# 6_I2C_Sensors.net
KiCad netlist of a schematic drawn in Altium Designer
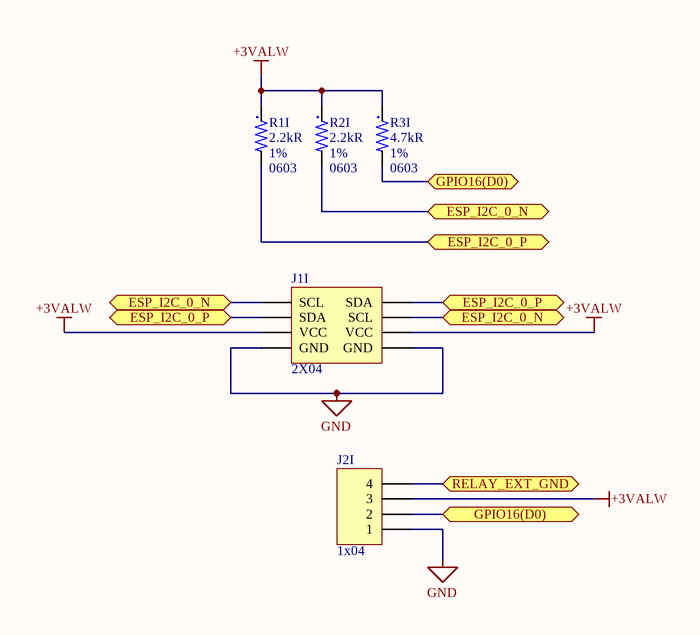
[diagram p0: 6_I2C_Sensors.SchDoc]

(export (version "E")
  (design (tool "Eeschema 10.0.6"))
  (components
    (comp (ref "J1I")
      (value "2X04")
      (footprint "PinHeader_2x04_P2.54mm_Vertical")
      (libsource (lib "Lib_Connector_PinHeader_2.54mm") (part "I2C_2X04_P2.54mm"))
    )
    (comp (ref "J2I")
      (value "1x04")
      (footprint "PinHeader_1x04_P2.54mm_Vertical")
      (libsource (lib "Lib_Connector_PinHeader_2.54mm") (part "PinHeader 1x04"))
    )
    (comp (ref "R1I")
      (value "2.2kR")
      (footprint "R0603-MFG")
      (description "SMD Chip Resistor, 2.2 kOhm, ± 1%, 100 mW, 0603 [1608 Metric], Thick Film, General Purpose")
      (fields
        (field (name "MANUFACTURER") "Yageo")
        (field (name "MANUFACTURER PART NUMBER") "RC0603FR-072K2L")
        (field (name "TOLERANCE") "1%")
        (field (name "CASE/PACKAGE") "0603")
      )
      (libsource (lib "Lib_Register_0603") (part "2.2K"))
    )
    (comp (ref "R2I")
      (value "2.2kR")
      (footprint "R0603-MFG")
      (description "SMD Chip Resistor, 2.2 kOhm, ± 1%, 100 mW, 0603 [1608 Metric], Thick Film, General Purpose")
      (fields
        (field (name "MANUFACTURER") "Yageo")
        (field (name "MANUFACTURER PART NUMBER") "RC0603FR-072K2L")
        (field (name "TOLERANCE") "1%")
        (field (name "CASE/PACKAGE") "0603")
      )
      (libsource (lib "Lib_Register_0603") (part "2.2K"))
    )
    (comp (ref "R3I")
      (value "4.7kR")
      (footprint "R0603-MFG")
      (description "SMD Chip Resistor, 4.7 kOhm, ± 1%, 100 mW, 0603 [1608 Metric], Thick Film, General Purpose")
      (fields
        (field (name "MANUFACTURER") "Yageo")
        (field (name "MANUFACTURER PART NUMBER") "AC0603FR-074K7L")
        (field (name "TOLERANCE") "1%")
        (field (name "CASE/PACKAGE") "0603")
      )
      (libsource (lib "Lib_Register_0603") (part "4.7K"))
    )
  )
  (nets
    (net (code "1") (name "+3VALW") (class "Default")
      (node (ref "J1I") (pin "3") (pinfunction "VCC_3") (pintype "passive"))
      (node (ref "J1I") (pin "4") (pinfunction "VCC_4") (pintype "passive"))
      (node (ref "J2I") (pin "3") (pinfunction "3_3") (pintype "passive"))
      (node (ref "R1I") (pin "1") (pinfunction "1_1") (pintype "passive"))
      (node (ref "R2I") (pin "1") (pinfunction "1_1") (pintype "passive"))
      (node (ref "R3I") (pin "1") (pinfunction "1_1") (pintype "passive"))
    )
    (net (code "2") (name "/ESP_I2C_0_N") (class "Default")
      (node (ref "J1I") (pin "5") (pinfunction "SCL_5") (pintype "passive"))
      (node (ref "J1I") (pin "8") (pinfunction "SCL_8") (pintype "passive"))
      (node (ref "R2I") (pin "2") (pinfunction "2_2") (pintype "passive"))
    )
    (net (code "3") (name "/ESP_I2C_0_P") (class "Default")
      (node (ref "J1I") (pin "6") (pinfunction "SDA_6") (pintype "passive"))
      (node (ref "J1I") (pin "7") (pinfunction "SDA_7") (pintype "passive"))
      (node (ref "R1I") (pin "2") (pinfunction "2_2") (pintype "passive"))
    )
    (net (code "4") (name "/GPIO16(D0)") (class "Default")
      (node (ref "J2I") (pin "2") (pinfunction "2_2") (pintype "passive"))
      (node (ref "R3I") (pin "2") (pinfunction "2_2") (pintype "passive"))
    )
    (net (code "5") (name "/RELAY_EXT_GND") (class "Default")
      (node (ref "J2I") (pin "4") (pinfunction "4_4") (pintype "passive"))
    )
    (net (code "6") (name "GND") (class "Default")
      (node (ref "J1I") (pin "1") (pinfunction "GND_1") (pintype "passive"))
      (node (ref "J1I") (pin "2") (pinfunction "GND_2") (pintype "passive"))
      (node (ref "J2I") (pin "1") (pinfunction "1_1") (pintype "passive"))
    )
  )
)
